# dual_header_card_60_100.net
KiCad netlist of a schematic drawn in Altium Designer
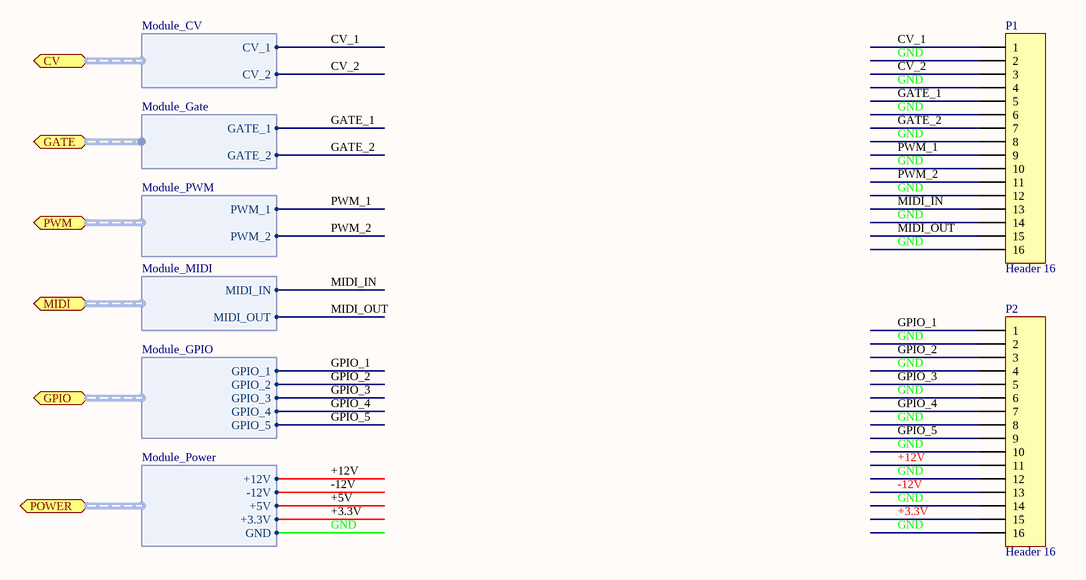
[diagram p0: dual_header_card_60_100.SchDoc]

(export (version "E")
  (design (tool "Eeschema 10.0.6"))
  (components
    (comp (ref "P1")
      (value "Header 16")
      (footprint "HDR1X16")
      (description "Header, 16-Pin")
      (fields (field (name "PUBLISHER") "Altium Limited"))
      (libsource (lib "Miscellaneous Connectors") (part "Header 16"))
    )
    (comp (ref "P2")
      (value "Header 16")
      (footprint "HDR1X16")
      (description "Header, 16-Pin")
      (fields (field (name "PUBLISHER") "Altium Limited"))
      (libsource (lib "Miscellaneous Connectors") (part "Header 16"))
    )
  )
  (nets
    (net (code "7") (name "/+3.3V") (class "Default")
      (node (ref "P2") (pin "15") (pinfunction "15_15") (pintype "passive"))
    )
    (net (code "9") (name "/+12V") (class "Default")
      (node (ref "P2") (pin "11") (pinfunction "11_11") (pintype "passive"))
    )
    (net (code "10") (name "/-12V") (class "Default")
      (node (ref "P2") (pin "13") (pinfunction "13_13") (pintype "passive"))
    )
    (net (code "11") (name "/CV_1") (class "Default")
      (node (ref "P1") (pin "1") (pinfunction "1_1") (pintype "passive"))
    )
    (net (code "12") (name "/CV_2") (class "Default")
      (node (ref "P1") (pin "3") (pinfunction "3_3") (pintype "passive"))
    )
    (net (code "13") (name "/GATE_1") (class "Default")
      (node (ref "P1") (pin "5") (pinfunction "5_5") (pintype "passive"))
    )
    (net (code "14") (name "/GATE_2") (class "Default")
      (node (ref "P1") (pin "7") (pinfunction "7_7") (pintype "passive"))
    )
    (net (code "15") (name "/GND") (class "Default")
      (node (ref "P1") (pin "10") (pinfunction "10_10") (pintype "passive"))
      (node (ref "P1") (pin "12") (pinfunction "12_12") (pintype "passive"))
      (node (ref "P1") (pin "14") (pinfunction "14_14") (pintype "passive"))
      (node (ref "P1") (pin "16") (pinfunction "16_16") (pintype "passive"))
      (node (ref "P1") (pin "2") (pinfunction "2_2") (pintype "passive"))
      (node (ref "P1") (pin "4") (pinfunction "4_4") (pintype "passive"))
      (node (ref "P1") (pin "6") (pinfunction "6_6") (pintype "passive"))
      (node (ref "P1") (pin "8") (pinfunction "8_8") (pintype "passive"))
      (node (ref "P2") (pin "10") (pinfunction "10_10") (pintype "passive"))
      (node (ref "P2") (pin "12") (pinfunction "12_12") (pintype "passive"))
      (node (ref "P2") (pin "14") (pinfunction "14_14") (pintype "passive"))
      (node (ref "P2") (pin "16") (pinfunction "16_16") (pintype "passive"))
      (node (ref "P2") (pin "2") (pinfunction "2_2") (pintype "passive"))
      (node (ref "P2") (pin "4") (pinfunction "4_4") (pintype "passive"))
      (node (ref "P2") (pin "6") (pinfunction "6_6") (pintype "passive"))
      (node (ref "P2") (pin "8") (pinfunction "8_8") (pintype "passive"))
    )
    (net (code "16") (name "/GPIO_1") (class "Default")
      (node (ref "P2") (pin "1") (pinfunction "1_1") (pintype "passive"))
    )
    (net (code "17") (name "/GPIO_2") (class "Default")
      (node (ref "P2") (pin "3") (pinfunction "3_3") (pintype "passive"))
    )
    (net (code "18") (name "/GPIO_3") (class "Default")
      (node (ref "P2") (pin "5") (pinfunction "5_5") (pintype "passive"))
    )
    (net (code "19") (name "/GPIO_4") (class "Default")
      (node (ref "P2") (pin "7") (pinfunction "7_7") (pintype "passive"))
    )
    (net (code "20") (name "/GPIO_5") (class "Default")
      (node (ref "P2") (pin "9") (pinfunction "9_9") (pintype "passive"))
    )
    (net (code "21") (name "/MIDI_IN") (class "Default")
      (node (ref "P1") (pin "13") (pinfunction "13_13") (pintype "passive"))
    )
    (net (code "22") (name "/MIDI_OUT") (class "Default")
      (node (ref "P1") (pin "15") (pinfunction "15_15") (pintype "passive"))
    )
    (net (code "23") (name "/PWM_1") (class "Default")
      (node (ref "P1") (pin "9") (pinfunction "9_9") (pintype "passive"))
    )
    (net (code "24") (name "/PWM_2") (class "Default")
      (node (ref "P1") (pin "11") (pinfunction "11_11") (pintype "passive"))
    )
  )
)
